# ESP_LoRa_ScaleSansotta.net
KiCad netlist of a schematic drawn in EAGLE
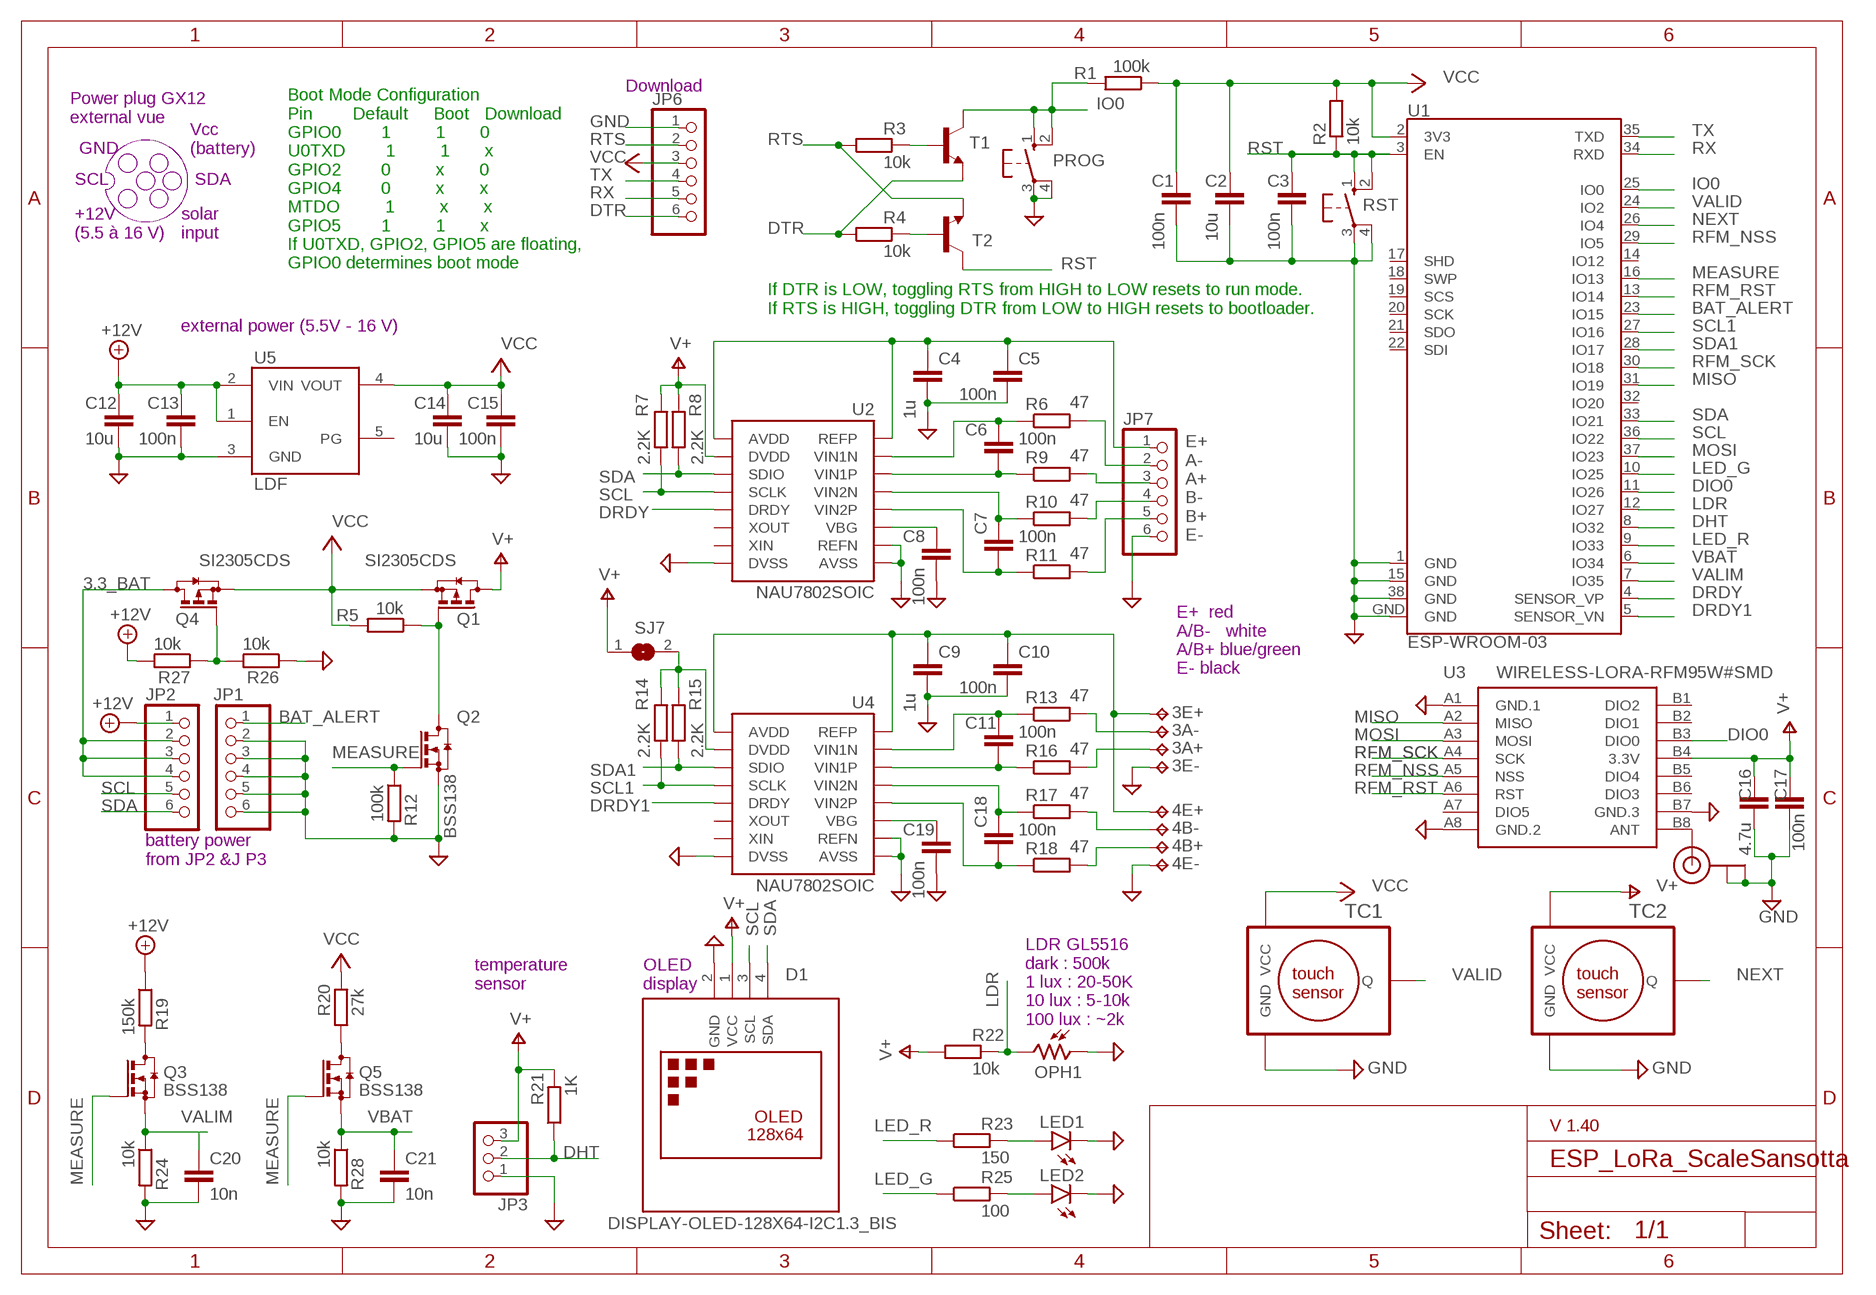
[diagram p0: schematic, sheet 1]

(export (version "E")
  (design (tool "Eeschema 10.0.6"))
  (components
    (comp (ref "3A+")
      (value "TPTP17SQ")
      (footprint "eagle-import:TP17SQ")
      (libsource (lib "eagle-import") (part "TPTP17SQ"))
    )
    (comp (ref "3A-")
      (value "TPTP17SQ")
      (footprint "eagle-import:TP17SQ")
      (libsource (lib "eagle-import") (part "TPTP17SQ"))
    )
    (comp (ref "3E+")
      (value "TPTP17SQ")
      (footprint "eagle-import:TP17SQ")
      (libsource (lib "eagle-import") (part "TPTP17SQ"))
    )
    (comp (ref "3E-")
      (value "TPTP17SQ")
      (footprint "eagle-import:TP17SQ")
      (libsource (lib "eagle-import") (part "TPTP17SQ"))
    )
    (comp (ref "4B+")
      (value "TPTP17SQ")
      (footprint "eagle-import:TP17SQ")
      (libsource (lib "eagle-import") (part "TPTP17SQ"))
    )
    (comp (ref "4B-")
      (value "TPTP17SQ")
      (footprint "eagle-import:TP17SQ")
      (libsource (lib "eagle-import") (part "TPTP17SQ"))
    )
    (comp (ref "4E+")
      (value "TPTP17SQ")
      (footprint "eagle-import:TP17SQ")
      (libsource (lib "eagle-import") (part "TPTP17SQ"))
    )
    (comp (ref "4E-")
      (value "TPTP17SQ")
      (footprint "eagle-import:TP17SQ")
      (libsource (lib "eagle-import") (part "TPTP17SQ"))
    )
    (comp (ref "C1")
      (value "100n")
      (footprint "eagle-import:C1206")
      (libsource (lib "eagle-import") (part "CC1206"))
    )
    (comp (ref "C2")
      (value "10u")
      (footprint "eagle-import:C1210")
      (libsource (lib "eagle-import") (part "CC1210"))
    )
    (comp (ref "C3")
      (value "100n")
      (footprint "eagle-import:C1206")
      (libsource (lib "eagle-import") (part "CC1206"))
    )
    (comp (ref "C4")
      (value "1u")
      (footprint "eagle-import:C1210")
      (libsource (lib "eagle-import") (part "CC1210"))
    )
    (comp (ref "C5")
      (value "100n")
      (footprint "eagle-import:C1206")
      (libsource (lib "eagle-import") (part "CC1206"))
    )
    (comp (ref "C6")
      (value "100n")
      (footprint "eagle-import:C1206")
      (libsource (lib "eagle-import") (part "CC1206"))
    )
    (comp (ref "C7")
      (value "100n")
      (footprint "eagle-import:C1206")
      (libsource (lib "eagle-import") (part "CC1206"))
    )
    (comp (ref "C8")
      (value "100n")
      (footprint "eagle-import:C1206")
      (libsource (lib "eagle-import") (part "CC1206"))
    )
    (comp (ref "C9")
      (value "1u")
      (footprint "eagle-import:C1210")
      (libsource (lib "eagle-import") (part "CC1210"))
    )
    (comp (ref "C10")
      (value "100n")
      (footprint "eagle-import:C1206")
      (libsource (lib "eagle-import") (part "CC1206"))
    )
    (comp (ref "C11")
      (value "100n")
      (footprint "eagle-import:C1206")
      (libsource (lib "eagle-import") (part "CC1206"))
    )
    (comp (ref "C12")
      (value "10u")
      (footprint "eagle-import:C1210")
      (libsource (lib "eagle-import") (part "CC1210"))
    )
    (comp (ref "C13")
      (value "100n")
      (footprint "eagle-import:C1206")
      (libsource (lib "eagle-import") (part "CC1206"))
    )
    (comp (ref "C14")
      (value "10u")
      (footprint "eagle-import:C1210")
      (libsource (lib "eagle-import") (part "CC1210"))
    )
    (comp (ref "C15")
      (value "100n")
      (footprint "eagle-import:C1206")
      (libsource (lib "eagle-import") (part "CC1206"))
    )
    (comp (ref "C16")
      (value "4.7u")
      (footprint "eagle-import:C1210")
      (libsource (lib "eagle-import") (part "CC1210"))
    )
    (comp (ref "C17")
      (value "100n")
      (footprint "eagle-import:C1206")
      (libsource (lib "eagle-import") (part "CC1206"))
    )
    (comp (ref "C18")
      (value "100n")
      (footprint "eagle-import:C1206")
      (libsource (lib "eagle-import") (part "CC1206"))
    )
    (comp (ref "C19")
      (value "100n")
      (footprint "eagle-import:C1206")
      (libsource (lib "eagle-import") (part "CC1206"))
    )
    (comp (ref "C20")
      (value "10n")
      (footprint "eagle-import:C1206")
      (libsource (lib "eagle-import") (part "CC1206"))
    )
    (comp (ref "C21")
      (value "10n")
      (footprint "eagle-import:C1206")
      (libsource (lib "eagle-import") (part "CC1206"))
    )
    (comp (ref "D1")
      (value "DISPLAY-OLED-128X64-I2C1.3_BIS")
      (footprint "eagle-import:DISPLAY-OLED-128X64-1.3-I2C_BIS")
      (libsource (lib "eagle-import") (part "DISPLAY-OLED-128X64-I2C1.3_BIS"))
    )
    (comp (ref "J1")
      (value "U.FL")
      (footprint "eagle-import:U.FL")
      (libsource (lib "eagle-import") (part "U.FL"))
    )
    (comp (ref "JP1")
      (value "PINHD-1X6")
      (footprint "eagle-import:1X06")
      (libsource (lib "eagle-import") (part "PINHD-1X6"))
    )
    (comp (ref "JP2")
      (value "PINHD-1X6")
      (footprint "eagle-import:1X06")
      (libsource (lib "eagle-import") (part "PINHD-1X6"))
    )
    (comp (ref "JP3")
      (value "PINHD-1X3")
      (footprint "eagle-import:1X03")
      (libsource (lib "eagle-import") (part "PINHD-1X3"))
    )
    (comp (ref "JP6")
      (value "PINHD-1X6")
      (footprint "eagle-import:1X06")
      (libsource (lib "eagle-import") (part "PINHD-1X6"))
    )
    (comp (ref "JP7")
      (value "PINHD-1X6")
      (footprint "eagle-import:1X06")
      (libsource (lib "eagle-import") (part "PINHD-1X6"))
    )
    (comp (ref "LED1")
      (value "LEDSMT1206")
      (footprint "eagle-import:1206")
      (libsource (lib "eagle-import") (part "LEDSMT1206"))
    )
    (comp (ref "LED2")
      (value "LEDSMT1206")
      (footprint "eagle-import:1206")
      (libsource (lib "eagle-import") (part "LEDSMT1206"))
    )
    (comp (ref "OPH1")
      (value "VT93N2")
      (footprint "eagle-import:VT900")
      (libsource (lib "eagle-import") (part "VT93N2"))
    )
    (comp (ref "PROG")
      (value "10-XX")
      (footprint "eagle-import:B3F-10XX")
      (fields (field (name "MPN") "B3F-1000"))
      (libsource (lib "eagle-import") (part "10-XX"))
    )
    (comp (ref "Q1")
      (value "SI2305CDS")
      (footprint "eagle-import:SOT23")
      (libsource (lib "eagle-import") (part "SI2305CDS"))
    )
    (comp (ref "Q2")
      (value "BSS138")
      (footprint "eagle-import:SOT23")
      (libsource (lib "eagle-import") (part "BSS138"))
    )
    (comp (ref "Q3")
      (value "BSS138")
      (footprint "eagle-import:SOT23")
      (libsource (lib "eagle-import") (part "BSS138"))
    )
    (comp (ref "Q4")
      (value "SI2305CDS")
      (footprint "eagle-import:SOT23")
      (libsource (lib "eagle-import") (part "SI2305CDS"))
    )
    (comp (ref "Q5")
      (value "BSS138")
      (footprint "eagle-import:SOT23")
      (libsource (lib "eagle-import") (part "BSS138"))
    )
    (comp (ref "R1")
      (value "100k")
      (footprint "eagle-import:R1206")
      (libsource (lib "eagle-import") (part "RR1206"))
    )
    (comp (ref "R2")
      (value "10k")
      (footprint "eagle-import:R1206")
      (libsource (lib "eagle-import") (part "RR1206"))
    )
    (comp (ref "R3")
      (value "10k")
      (footprint "eagle-import:R1206")
      (libsource (lib "eagle-import") (part "RR1206"))
    )
    (comp (ref "R4")
      (value "10k")
      (footprint "eagle-import:R1206")
      (libsource (lib "eagle-import") (part "RR1206"))
    )
    (comp (ref "R5")
      (value "10k")
      (footprint "eagle-import:R1206")
      (libsource (lib "eagle-import") (part "RR1206"))
    )
    (comp (ref "R6")
      (value "47")
      (footprint "eagle-import:R1206")
      (libsource (lib "eagle-import") (part "RR1206"))
    )
    (comp (ref "R7")
      (value "2.2K")
      (footprint "eagle-import:R1206")
      (libsource (lib "eagle-import") (part "RR1206"))
    )
    (comp (ref "R8")
      (value "2.2K")
      (footprint "eagle-import:R1206")
      (libsource (lib "eagle-import") (part "RR1206"))
    )
    (comp (ref "R9")
      (value "47")
      (footprint "eagle-import:R1206")
      (libsource (lib "eagle-import") (part "RR1206"))
    )
    (comp (ref "R10")
      (value "47")
      (footprint "eagle-import:R1206")
      (libsource (lib "eagle-import") (part "RR1206"))
    )
    (comp (ref "R11")
      (value "47")
      (footprint "eagle-import:R1206")
      (libsource (lib "eagle-import") (part "RR1206"))
    )
    (comp (ref "R12")
      (value "100k")
      (footprint "eagle-import:R1206")
      (libsource (lib "eagle-import") (part "RR1206"))
    )
    (comp (ref "R13")
      (value "47")
      (footprint "eagle-import:R1206")
      (libsource (lib "eagle-import") (part "RR1206"))
    )
    (comp (ref "R14")
      (value "2.2K")
      (footprint "eagle-import:R1206")
      (libsource (lib "eagle-import") (part "RR1206"))
    )
    (comp (ref "R15")
      (value "2.2K")
      (footprint "eagle-import:R1206")
      (libsource (lib "eagle-import") (part "RR1206"))
    )
    (comp (ref "R16")
      (value "47")
      (footprint "eagle-import:R1206")
      (libsource (lib "eagle-import") (part "RR1206"))
    )
    (comp (ref "R17")
      (value "47")
      (footprint "eagle-import:R1206")
      (libsource (lib "eagle-import") (part "RR1206"))
    )
    (comp (ref "R18")
      (value "47")
      (footprint "eagle-import:R1206")
      (libsource (lib "eagle-import") (part "RR1206"))
    )
    (comp (ref "R19")
      (value "150k")
      (footprint "eagle-import:R1206")
      (libsource (lib "eagle-import") (part "RR1206"))
    )
    (comp (ref "R20")
      (value "27k")
      (footprint "eagle-import:R1206")
      (libsource (lib "eagle-import") (part "RR1206"))
    )
    (comp (ref "R21")
      (value "1K")
      (footprint "eagle-import:R1206")
      (libsource (lib "eagle-import") (part "RR1206"))
    )
    (comp (ref "R22")
      (value "10k")
      (footprint "eagle-import:R1206")
      (libsource (lib "eagle-import") (part "RR1206"))
    )
    (comp (ref "R23")
      (value "150")
      (footprint "eagle-import:R1206")
      (libsource (lib "eagle-import") (part "RR1206"))
    )
    (comp (ref "R24")
      (value "10k")
      (footprint "eagle-import:R1206")
      (libsource (lib "eagle-import") (part "RR1206"))
    )
    (comp (ref "R25")
      (value "100")
      (footprint "eagle-import:R1206")
      (libsource (lib "eagle-import") (part "RR1206"))
    )
    (comp (ref "R26")
      (value "10k")
      (footprint "eagle-import:R1206")
      (libsource (lib "eagle-import") (part "RR1206"))
    )
    (comp (ref "R27")
      (value "10k")
      (footprint "eagle-import:R1206")
      (libsource (lib "eagle-import") (part "RR1206"))
    )
    (comp (ref "R28")
      (value "10k")
      (footprint "eagle-import:R1206")
      (libsource (lib "eagle-import") (part "RR1206"))
    )
    (comp (ref "RST")
      (value "10-XX")
      (footprint "eagle-import:B3F-10XX")
      (fields (field (name "MPN") "B3F-1000"))
      (libsource (lib "eagle-import") (part "10-XX"))
    )
    (comp (ref "SJ7") (value "SJ") (footprint "eagle-import:SJ") (libsource (lib "eagle-import") (part "SJ")))
    (comp (ref "T1")
      (value "MMBT2222ALT1-NPN-SOT23-BEC")
      (footprint "eagle-import:SOT23-BEC")
      (libsource (lib "eagle-import") (part "-NPN-SOT23-BECMMBT2222ALT1"))
    )
    (comp (ref "T2")
      (value "MMBT2222ALT1-NPN-SOT23-BEC")
      (footprint "eagle-import:SOT23-BEC")
      (libsource (lib "eagle-import") (part "-NPN-SOT23-BECMMBT2222ALT1"))
    )
    (comp (ref "TC1")
      (value "TTP223R_H")
      (footprint "eagle-import:TTP233RED_H")
      (libsource (lib "eagle-import") (part "TTP223R_H"))
    )
    (comp (ref "TC2")
      (value "TTP223R_H")
      (footprint "eagle-import:TTP233RED_H")
      (libsource (lib "eagle-import") (part "TTP223R_H"))
    )
    (comp (ref "U1")
      (value "ESP-WROOM-03")
      (footprint "eagle-import:ESP-WROOM-03")
      (libsource (lib "eagle-import") (part "ESP-WROOM-03"))
    )
    (comp (ref "U2")
      (value "NAU7802SOIC")
      (footprint "eagle-import:SO16")
      (libsource (lib "eagle-import") (part "NAU7802SOIC"))
    )
    (comp (ref "U3")
      (value "WIRELESS-LORA-RFM95W#SMD")
      (footprint "eagle-import:WIRELESS-LORA-RFM95W#SMD")
      (libsource (lib "eagle-import") (part "WIRELESS-LORA-RFM95W#SMD"))
    )
    (comp (ref "U4")
      (value "NAU7802SOIC")
      (footprint "eagle-import:SO16")
      (libsource (lib "eagle-import") (part "NAU7802SOIC"))
    )
    (comp (ref "U5")
      (value "LDF3.3")
      (footprint "eagle-import:PPAK")
      (libsource (lib "eagle-import") (part "LDF3.3"))
    )
  )
  (nets
    (net (code "1") (name "+12V") (class "Default")
      (node (ref "C12") (pin "1") (pinfunction "1_1") (pintype "passive"))
      (node (ref "C13") (pin "1") (pinfunction "1_1") (pintype "passive"))
      (node (ref "JP2") (pin "1") (pinfunction "1_1") (pintype "passive"))
      (node (ref "R19") (pin "1") (pinfunction "1_1") (pintype "passive"))
      (node (ref "R27") (pin "2") (pinfunction "2_2") (pintype "passive"))
      (node (ref "U5") (pin "1") (pinfunction "EN_1") (pintype "input"))
      (node (ref "U5") (pin "2") (pinfunction "VIN_2") (pintype "power_in"))
    )
    (net (code "2") (name "/3.3_BAT") (class "Default")
      (node (ref "JP2") (pin "2") (pinfunction "2_2") (pintype "passive"))
      (node (ref "JP2") (pin "3") (pinfunction "3_3") (pintype "passive"))
      (node (ref "JP2") (pin "4") (pinfunction "4_4") (pintype "passive"))
      (node (ref "Q4") (pin "3") (pinfunction "D_3") (pintype "passive"))
    )
    (net (code "3") (name "/BAT_ALERT") (class "Default")
      (node (ref "JP1") (pin "1") (pinfunction "1_1") (pintype "passive"))
      (node (ref "U1") (pin "23") (pinfunction "IO15_23") (pintype "bidirectional"))
    )
    (net (code "4") (name "/DHT") (class "Default")
      (node (ref "JP3") (pin "2") (pinfunction "2_2") (pintype "passive"))
      (node (ref "R21") (pin "1") (pinfunction "1_1") (pintype "passive"))
      (node (ref "U1") (pin "8") (pinfunction "IO32_8") (pintype "bidirectional"))
    )
    (net (code "5") (name "/DIO0") (class "Default")
      (node (ref "U1") (pin "11") (pinfunction "IO26_11") (pintype "bidirectional"))
      (node (ref "U3") (pin "B3") (pinfunction "DIO0_B3") (pintype "bidirectional"))
    )
    (net (code "6") (name "/DRDY") (class "Default")
      (node (ref "U1") (pin "4") (pinfunction "SENSOR_VP_4") (pintype "bidirectional"))
      (node (ref "U2") (pin "12") (pinfunction "DRDY_12") (pintype "bidirectional"))
    )
    (net (code "7") (name "/DRDY1") (class "Default")
      (node (ref "U1") (pin "5") (pinfunction "SENSOR_VN_5") (pintype "bidirectional"))
      (node (ref "U4") (pin "12") (pinfunction "DRDY_12") (pintype "bidirectional"))
    )
    (net (code "8") (name "/DTR") (class "Default")
      (node (ref "JP6") (pin "6") (pinfunction "6_6") (pintype "passive"))
      (node (ref "R4") (pin "1") (pinfunction "1_1") (pintype "passive"))
      (node (ref "T1") (pin "E") (pinfunction "E_E") (pintype "passive"))
    )
    (net (code "9") (name "/IO0") (class "Default")
      (node (ref "PROG") (pin "1") (pinfunction "S_1") (pintype "passive"))
      (node (ref "PROG") (pin "2") (pinfunction "S1_2") (pintype "passive"))
      (node (ref "R1") (pin "2") (pinfunction "2_2") (pintype "passive"))
      (node (ref "T1") (pin "C") (pinfunction "C_C") (pintype "passive"))
      (node (ref "U1") (pin "25") (pinfunction "IO0_25") (pintype "bidirectional"))
    )
    (net (code "10") (name "/LDR") (class "Default")
      (node (ref "OPH1") (pin "2") (pinfunction "2_2") (pintype "passive"))
      (node (ref "R22") (pin "2") (pinfunction "2_2") (pintype "passive"))
      (node (ref "U1") (pin "12") (pinfunction "IO27_12") (pintype "bidirectional"))
    )
    (net (code "11") (name "/LED_G") (class "Default")
      (node (ref "R25") (pin "1") (pinfunction "1_1") (pintype "passive"))
      (node (ref "U1") (pin "10") (pinfunction "IO25_10") (pintype "bidirectional"))
    )
    (net (code "12") (name "/LED_R") (class "Default")
      (node (ref "R23") (pin "1") (pinfunction "1_1") (pintype "passive"))
      (node (ref "U1") (pin "9") (pinfunction "IO33_9") (pintype "bidirectional"))
    )
    (net (code "13") (name "/MEASURE") (class "Default")
      (node (ref "Q2") (pin "1") (pinfunction "G_1") (pintype "passive"))
      (node (ref "Q3") (pin "1") (pinfunction "G_1") (pintype "passive"))
      (node (ref "Q5") (pin "1") (pinfunction "G_1") (pintype "passive"))
      (node (ref "R12") (pin "1") (pinfunction "1_1") (pintype "passive"))
      (node (ref "U1") (pin "16") (pinfunction "IO13_16") (pintype "bidirectional"))
    )
    (net (code "14") (name "/MISO") (class "Default")
      (node (ref "U1") (pin "31") (pinfunction "IO19_31") (pintype "bidirectional"))
      (node (ref "U3") (pin "A2") (pinfunction "MISO_A2") (pintype "bidirectional"))
    )
    (net (code "15") (name "/MOSI") (class "Default")
      (node (ref "U1") (pin "37") (pinfunction "IO23_37") (pintype "bidirectional"))
      (node (ref "U3") (pin "A3") (pinfunction "MOSI_A3") (pintype "bidirectional"))
    )
    (net (code "16") (name "/NEXT") (class "Default")
      (node (ref "TC2") (pin "P$2") (pinfunction "Q_P$2") (pintype "power_in"))
      (node (ref "U1") (pin "26") (pinfunction "IO4_26") (pintype "bidirectional"))
    )
    (net (code "17") (name "/PG") (class "Default")
      (node (ref "U5") (pin "5") (pinfunction "PG_5") (pintype "power_in"))
    )
    (net (code "18") (name "/RFM_NSS") (class "Default")
      (node (ref "U1") (pin "29") (pinfunction "IO5_29") (pintype "bidirectional"))
      (node (ref "U3") (pin "A5") (pinfunction "NSS_A5") (pintype "bidirectional"))
    )
    (net (code "19") (name "/RFM_RST") (class "Default")
      (node (ref "U1") (pin "13") (pinfunction "IO14_13") (pintype "bidirectional"))
      (node (ref "U3") (pin "A6") (pinfunction "RST_A6") (pintype "bidirectional"))
    )
    (net (code "20") (name "/RFM_SCK") (class "Default")
      (node (ref "U1") (pin "30") (pinfunction "IO18_30") (pintype "bidirectional"))
      (node (ref "U3") (pin "A4") (pinfunction "SCK_A4") (pintype "bidirectional"))
    )
    (net (code "21") (name "/RST") (class "Default")
      (node (ref "C3") (pin "1") (pinfunction "1_1") (pintype "passive"))
      (node (ref "R2") (pin "1") (pinfunction "1_1") (pintype "passive"))
      (node (ref "RST") (pin "1") (pinfunction "S_1") (pintype "passive"))
      (node (ref "RST") (pin "2") (pinfunction "S1_2") (pintype "passive"))
      (node (ref "T2") (pin "C") (pinfunction "C_C") (pintype "passive"))
      (node (ref "U1") (pin "3") (pinfunction "EN_3") (pintype "bidirectional"))
    )
    (net (code "22") (name "/RTS") (class "Default")
      (node (ref "JP6") (pin "2") (pinfunction "2_2") (pintype "passive"))
      (node (ref "R3") (pin "1") (pinfunction "1_1") (pintype "passive"))
      (node (ref "T2") (pin "E") (pinfunction "E_E") (pintype "passive"))
    )
    (net (code "23") (name "/RX") (class "Default")
      (node (ref "JP6") (pin "5") (pinfunction "5_5") (pintype "passive"))
      (node (ref "U1") (pin "34") (pinfunction "RXD_34") (pintype "bidirectional"))
    )
    (net (code "24") (name "/SCL") (class "Default")
      (node (ref "D1") (pin "3") (pinfunction "SCL_3") (pintype "bidirectional"))
      (node (ref "JP2") (pin "5") (pinfunction "5_5") (pintype "passive"))
      (node (ref "R7") (pin "1") (pinfunction "1_1") (pintype "passive"))
      (node (ref "U1") (pin "36") (pinfunction "IO22_36") (pintype "bidirectional"))
      (node (ref "U2") (pin "13") (pinfunction "SCLK_13") (pintype "bidirectional"))
    )
    (net (code "25") (name "/SCL1") (class "Default")
      (node (ref "R14") (pin "1") (pinfunction "1_1") (pintype "passive"))
      (node (ref "U1") (pin "27") (pinfunction "IO16_27") (pintype "bidirectional"))
      (node (ref "U4") (pin "13") (pinfunction "SCLK_13") (pintype "bidirectional"))
    )
    (net (code "26") (name "/SDA") (class "Default")
      (node (ref "D1") (pin "4") (pinfunction "SDA_4") (pintype "bidirectional"))
      (node (ref "JP2") (pin "6") (pinfunction "6_6") (pintype "passive"))
      (node (ref "R8") (pin "1") (pinfunction "1_1") (pintype "passive"))
      (node (ref "U1") (pin "33") (pinfunction "IO21_33") (pintype "bidirectional"))
      (node (ref "U2") (pin "14") (pinfunction "SDIO_14") (pintype "bidirectional"))
    )
    (net (code "27") (name "/SDA1") (class "Default")
      (node (ref "R15") (pin "1") (pinfunction "1_1") (pintype "passive"))
      (node (ref "U1") (pin "28") (pinfunction "IO17_28") (pintype "bidirectional"))
      (node (ref "U4") (pin "14") (pinfunction "SDIO_14") (pintype "bidirectional"))
    )
    (net (code "28") (name "/TX") (class "Default")
      (node (ref "JP6") (pin "4") (pinfunction "4_4") (pintype "passive"))
      (node (ref "U1") (pin "35") (pinfunction "TXD_35") (pintype "bidirectional"))
    )
    (net (code "29") (name "/VALID") (class "Default")
      (node (ref "TC1") (pin "P$2") (pinfunction "Q_P$2") (pintype "power_in"))
      (node (ref "U1") (pin "24") (pinfunction "IO2_24") (pintype "bidirectional"))
    )
    (net (code "30") (name "/VALIM") (class "Default")
      (node (ref "C20") (pin "1") (pinfunction "1_1") (pintype "passive"))
      (node (ref "Q3") (pin "2") (pinfunction "S_2") (pintype "passive"))
      (node (ref "R24") (pin "1") (pinfunction "1_1") (pintype "passive"))
      (node (ref "U1") (pin "7") (pinfunction "IO35_7") (pintype "bidirectional"))
    )
    (net (code "31") (name "/VBAT") (class "Default")
      (node (ref "C21") (pin "1") (pinfunction "1_1") (pintype "passive"))
      (node (ref "Q5") (pin "2") (pinfunction "S_2") (pintype "passive"))
      (node (ref "R28") (pin "1") (pinfunction "1_1") (pintype "passive"))
      (node (ref "U1") (pin "6") (pinfunction "IO34_6") (pintype "bidirectional"))
    )
    (net (code "32") (name "GND") (class "Default")
      (node (ref "3E-") (pin "TP") (pinfunction "TP_TP") (pintype "input"))
      (node (ref "4E-") (pin "TP") (pinfunction "TP_TP") (pintype "input"))
      (node (ref "C1") (pin "2") (pinfunction "2_2") (pintype "passive"))
      (node (ref "C10") (pin "2") (pinfunction "2_2") (pintype "passive"))
      (node (ref "C12") (pin "2") (pinfunction "2_2") (pintype "passive"))
      (node (ref "C13") (pin "2") (pinfunction "2_2") (pintype "passive"))
      (node (ref "C14") (pin "2") (pinfunction "2_2") (pintype "passive"))
      (node (ref "C15") (pin "2") (pinfunction "2_2") (pintype "passive"))
      (node (ref "C16") (pin "2") (pinfunction "2_2") (pintype "passive"))
      (node (ref "C17") (pin "2") (pinfunction "2_2") (pintype "passive"))
      (node (ref "C19") (pin "2") (pinfunction "2_2") (pintype "passive"))
      (node (ref "C2") (pin "2") (pinfunction "2_2") (pintype "passive"))
      (node (ref "C20") (pin "2") (pinfunction "2_2") (pintype "passive"))
      (node (ref "C21") (pin "2") (pinfunction "2_2") (pintype "passive"))
      (node (ref "C3") (pin "2") (pinfunction "2_2") (pintype "passive"))
      (node (ref "C4") (pin "2") (pinfunction "2_2") (pintype "passive"))
      (node (ref "C5") (pin "2") (pinfunction "2_2") (pintype "passive"))
      (node (ref "C8") (pin "2") (pinfunction "2_2") (pintype "passive"))
      (node (ref "C9") (pin "2") (pinfunction "2_2") (pintype "passive"))
      (node (ref "D1") (pin "2") (pinfunction "GND_2") (pintype "power_in"))
      (node (ref "J1") (pin "1") (pinfunction "GND_1") (pintype "passive"))
      (node (ref "J1") (pin "2") (pinfunction "GND_2") (pintype "passive"))
      (node (ref "JP1") (pin "2") (pinfunction "2_2") (pintype "passive"))
      (node (ref "JP1") (pin "3") (pinfunction "3_3") (pintype "passive"))
      (node (ref "JP1") (pin "4") (pinfunction "4_4") (pintype "passive"))
      (node (ref "JP1") (pin "5") (pinfunction "5_5") (pintype "passive"))
      (node (ref "JP1") (pin "6") (pinfunction "6_6") (pintype "passive"))
      (node (ref "JP3") (pin "1") (pinfunction "1_1") (pintype "passive"))
      (node (ref "JP6") (pin "1") (pinfunction "1_1") (pintype "passive"))
      (node (ref "JP7") (pin "6") (pinfunction "6_6") (pintype "passive"))
      (node (ref "LED1") (pin "C") (pinfunction "C_C") (pintype "passive"))
      (node (ref "LED2") (pin "C") (pinfunction "C_C") (pintype "passive"))
      (node (ref "OPH1") (pin "1") (pinfunction "1_1") (pintype "passive"))
      (node (ref "PROG") (pin "3") (pinfunction "P_3") (pintype "passive"))
      (node (ref "PROG") (pin "4") (pinfunction "P1_4") (pintype "passive"))
      (node (ref "Q2") (pin "2") (pinfunction "S_2") (pintype "passive"))
      (node (ref "R12") (pin "2") (pinfunction "2_2") (pintype "passive"))
      (node (ref "R24") (pin "2") (pinfunction "2_2") (pintype "passive"))
      (node (ref "R26") (pin "1") (pinfunction "1_1") (pintype "passive"))
      (node (ref "R28") (pin "2") (pinfunction "2_2") (pintype "passive"))
      (node (ref "RST") (pin "3") (pinfunction "P_3") (pintype "passive"))
      (node (ref "RST") (pin "4") (pinfunction "P1_4") (pintype "passive"))
      (node (ref "TC1") (pin "P$3") (pinfunction "GND_P$3") (pintype "power_in"))
      (node (ref "TC2") (pin "P$3") (pinfunction "GND_P$3") (pintype "power_in"))
      (node (ref "U1") (pin "1") (pinfunction "GND_1") (pintype "bidirectional"))
      (node (ref "U1") (pin "15") (pinfunction "GND_15") (pintype "bidirectional"))
      (node (ref "U1") (pin "38") (pinfunction "GND_38") (pintype "bidirectional"))
      (node (ref "U1") (pin "GND") (pinfunction "GND_GND") (pintype "bidirectional"))
      (node (ref "U2") (pin "7") (pinfunction "REFN_7") (pintype "bidirectional"))
      (node (ref "U2") (pin "8") (pinfunction "AVSS_8") (pintype "bidirectional"))
      (node (ref "U2") (pin "9") (pinfunction "DVSS_9") (pintype "bidirectional"))
      (node (ref "U3") (pin "A1") (pinfunction "GND.1_A1") (pintype "power_in"))
      (node (ref "U3") (pin "A8") (pinfunction "GND.2_A8") (pintype "power_in"))
      (node (ref "U3") (pin "B7") (pinfunction "GND.3_B7") (pintype "power_in"))
      (node (ref "U4") (pin "7") (pinfunction "REFN_7") (pintype "bidirectional"))
      (node (ref "U4") (pin "8") (pinfunction "AVSS_8") (pintype "bidirectional"))
      (node (ref "U4") (pin "9") (pinfunction "DVSS_9") (pintype "bidirectional"))
      (node (ref "U5") (pin "3") (pinfunction "GND_3") (pintype "power_in"))
    )
    (net (code "33") (name "Net-(3A+-PadTP)") (class "Default")
      (node (ref "3A+") (pin "TP") (pinfunction "TP_TP") (pintype "input"))
      (node (ref "R16") (pin "2") (pinfunction "2_2") (pintype "passive"))
    )
    (net (code "34") (name "Net-(3A--PadTP)") (class "Default")
      (node (ref "3A-") (pin "TP") (pinfunction "TP_TP") (pintype "input"))
      (node (ref "R13") (pin "2") (pinfunction "2_2") (pintype "passive"))
    )
    (net (code "35") (name "Net-(4B+-PadTP)") (class "Default")
      (node (ref "4B+") (pin "TP") (pinfunction "TP_TP") (pintype "input"))
      (node (ref "R18") (pin "2") (pinfunction "2_2") (pintype "passive"))
    )
    (net (code "36") (name "Net-(4B--PadTP)") (class "Default")
      (node (ref "4B-") (pin "TP") (pinfunction "TP_TP") (pintype "input"))
      (node (ref "R17") (pin "2") (pinfunction "2_2") (pintype "passive"))
    )
    (net (code "37") (name "Net-(J1-SIGNAL)") (class "Default")
      (node (ref "J1") (pin "3") (pinfunction "SIGNAL_3") (pintype "passive"))
      (node (ref "U3") (pin "B8") (pinfunction "ANT_B8") (pintype "passive"))
    )
    (net (code "38") (name "Net-(JP7-Pad2)") (class "Default")
      (node (ref "JP7") (pin "2") (pinfunction "2_2") (pintype "passive"))
      (node (ref "R6") (pin "2") (pinfunction "2_2") (pintype "passive"))
    )
    (net (code "39") (name "Net-(JP7-Pad3)") (class "Default")
      (node (ref "JP7") (pin "3") (pinfunction "3_3") (pintype "passive"))
      (node (ref "R9") (pin "2") (pinfunction "2_2") (pintype "passive"))
    )
    (net (code "40") (name "Net-(JP7-Pad4)") (class "Default")
      (node (ref "JP7") (pin "4") (pinfunction "4_4") (pintype "passive"))
      (node (ref "R10") (pin "2") (pinfunction "2_2") (pintype "passive"))
    )
    (net (code "41") (name "Net-(JP7-Pad5)") (class "Default")
      (node (ref "JP7") (pin "5") (pinfunction "5_5") (pintype "passive"))
      (node (ref "R11") (pin "2") (pinfunction "2_2") (pintype "passive"))
    )
    (net (code "42") (name "Net-(LED1-PadA)") (class "Default")
      (node (ref "LED1") (pin "A") (pinfunction "A_A") (pintype "passive"))
      (node (ref "R23") (pin "2") (pinfunction "2_2") (pintype "passive"))
    )
    (net (code "43") (name "Net-(LED2-PadA)") (class "Default")
      (node (ref "LED2") (pin "A") (pinfunction "A_A") (pintype "passive"))
      (node (ref "R25") (pin "2") (pinfunction "2_2") (pintype "passive"))
    )
    (net (code "44") (name "Net-(Q1-G)") (class "Default")
      (node (ref "Q1") (pin "1") (pinfunction "G_1") (pintype "passive"))
      (node (ref "Q2") (pin "3") (pinfunction "D_3") (pintype "passive"))
      (node (ref "R5") (pin "1") (pinfunction "1_1") (pintype "passive"))
    )
    (net (code "45") (name "Net-(Q3-D)") (class "Default")
      (node (ref "Q3") (pin "3") (pinfunction "D_3") (pintype "passive"))
      (node (ref "R19") (pin "2") (pinfunction "2_2") (pintype "passive"))
    )
    (net (code "46") (name "Net-(Q4-G)") (class "Default")
      (node (ref "Q4") (pin "1") (pinfunction "G_1") (pintype "passive"))
      (node (ref "R26") (pin "2") (pinfunction "2_2") (pintype "passive"))
      (node (ref "R27") (pin "1") (pinfunction "1_1") (pintype "passive"))
    )
    (net (code "47") (name "Net-(Q5-D)") (class "Default")
      (node (ref "Q5") (pin "3") (pinfunction "D_3") (pintype "passive"))
      (node (ref "R20") (pin "1") (pinfunction "1_1") (pintype "passive"))
    )
    (net (code "48") (name "Net-(R3-Pad2)") (class "Default")
      (node (ref "R3") (pin "2") (pinfunction "2_2") (pintype "passive"))
      (node (ref "T1") (pin "B") (pinfunction "B_B") (pintype "passive"))
    )
    (net (code "49") (name "Net-(R4-Pad2)") (class "Default")
      (node (ref "R4") (pin "2") (pinfunction "2_2") (pintype "passive"))
      (node (ref "T2") (pin "B") (pinfunction "B_B") (pintype "passive"))
    )
    (net (code "50") (name "Net-(U2-AVDD)") (class "Default")
      (node (ref "C4") (pin "1") (pinfunction "1_1") (pintype "passive"))
      (node (ref "C5") (pin "1") (pinfunction "1_1") (pintype "passive"))
      (node (ref "JP7") (pin "1") (pinfunction "1_1") (pintype "passive"))
      (node (ref "U2") (pin "1") (pinfunction "REFP_1") (pintype "bidirectional"))
      (node (ref "U2") (pin "16") (pinfunction "AVDD_16") (pintype "bidirectional"))
    )
    (net (code "51") (name "Net-(U2-VBG)") (class "Default")
      (node (ref "C8") (pin "1") (pinfunction "1_1") (pintype "passive"))
      (node (ref "U2") (pin "6") (pinfunction "VBG_6") (pintype "bidirectional"))
    )
    (net (code "52") (name "Net-(U2-VIN1N)") (class "Default")
      (node (ref "C6") (pin "1") (pinfunction "1_1") (pintype "passive"))
      (node (ref "R6") (pin "1") (pinfunction "1_1") (pintype "passive"))
      (node (ref "U2") (pin "2") (pinfunction "VIN1N_2") (pintype "bidirectional"))
    )
    (net (code "53") (name "Net-(U2-VIN1P)") (class "Default")
      (node (ref "C6") (pin "2") (pinfunction "2_2") (pintype "passive"))
      (node (ref "R9") (pin "1") (pinfunction "1_1") (pintype "passive"))
      (node (ref "U2") (pin "3") (pinfunction "VIN1P_3") (pintype "bidirectional"))
    )
    (net (code "54") (name "Net-(U2-VIN2N)") (class "Default")
      (node (ref "C7") (pin "1") (pinfunction "1_1") (pintype "passive"))
      (node (ref "R10") (pin "1") (pinfunction "1_1") (pintype "passive"))
      (node (ref "U2") (pin "4") (pinfunction "VIN2N_4") (pintype "bidirectional"))
    )
    (net (code "55") (name "Net-(U2-VIN2P)") (class "Default")
      (node (ref "C7") (pin "2") (pinfunction "2_2") (pintype "passive"))
      (node (ref "R11") (pin "1") (pinfunction "1_1") (pintype "passive"))
      (node (ref "U2") (pin "5") (pinfunction "VIN2P_5") (pintype "bidirectional"))
    )
    (net (code "56") (name "Net-(U4-AVDD)") (class "Default")
      (node (ref "3E+") (pin "TP") (pinfunction "TP_TP") (pintype "input"))
      (node (ref "4E+") (pin "TP") (pinfunction "TP_TP") (pintype "input"))
      (node (ref "C10") (pin "1") (pinfunction "1_1") (pintype "passive"))
      (node (ref "C9") (pin "1") (pinfunction "1_1") (pintype "passive"))
      (node (ref "U4") (pin "1") (pinfunction "REFP_1") (pintype "bidirectional"))
      (node (ref "U4") (pin "16") (pinfunction "AVDD_16") (pintype "bidirectional"))
    )
    (net (code "57") (name "Net-(U4-DVDD)") (class "Default")
      (node (ref "R14") (pin "2") (pinfunction "2_2") (pintype "passive"))
      (node (ref "R15") (pin "2") (pinfunction "2_2") (pintype "passive"))
      (node (ref "SJ7") (pin "2") (pinfunction "2_2") (pintype "passive"))
      (node (ref "U4") (pin "15") (pinfunction "DVDD_15") (pintype "bidirectional"))
    )
    (net (code "58") (name "Net-(U4-VBG)") (class "Default")
      (node (ref "C19") (pin "1") (pinfunction "1_1") (pintype "passive"))
      (node (ref "U4") (pin "6") (pinfunction "VBG_6") (pintype "bidirectional"))
    )
    (net (code "59") (name "Net-(U4-VIN1N)") (class "Default")
      (node (ref "C11") (pin "1") (pinfunction "1_1") (pintype "passive"))
      (node (ref "R13") (pin "1") (pinfunction "1_1") (pintype "passive"))
      (node (ref "U4") (pin "2") (pinfunction "VIN1N_2") (pintype "bidirectional"))
    )
    (net (code "60") (name "Net-(U4-VIN1P)") (class "Default")
      (node (ref "C11") (pin "2") (pinfunction "2_2") (pintype "passive"))
      (node (ref "R16") (pin "1") (pinfunction "1_1") (pintype "passive"))
      (node (ref "U4") (pin "3") (pinfunction "VIN1P_3") (pintype "bidirectional"))
    )
    (net (code "61") (name "Net-(U4-VIN2N)") (class "Default")
      (node (ref "C18") (pin "1") (pinfunction "1_1") (pintype "passive"))
      (node (ref "R17") (pin "1") (pinfunction "1_1") (pintype "passive"))
      (node (ref "U4") (pin "4") (pinfunction "VIN2N_4") (pintype "bidirectional"))
    )
    (net (code "62") (name "Net-(U4-VIN2P)") (class "Default")
      (node (ref "C18") (pin "2") (pinfunction "2_2") (pintype "passive"))
      (node (ref "R18") (pin "1") (pinfunction "1_1") (pintype "passive"))
      (node (ref "U4") (pin "5") (pinfunction "VIN2P_5") (pintype "bidirectional"))
    )
    (net (code "63") (name "V+") (class "Default")
      (node (ref "C16") (pin "1") (pinfunction "1_1") (pintype "passive"))
      (node (ref "C17") (pin "1") (pinfunction "1_1") (pintype "passive"))
      (node (ref "D1") (pin "1") (pinfunction "VCC_1") (pintype "power_in"))
      (node (ref "JP3") (pin "3") (pinfunction "3_3") (pintype "passive"))
      (node (ref "Q1") (pin "3") (pinfunction "D_3") (pintype "passive"))
      (node (ref "R21") (pin "2") (pinfunction "2_2") (pintype "passive"))
      (node (ref "R22") (pin "1") (pinfunction "1_1") (pintype "passive"))
      (node (ref "R7") (pin "2") (pinfunction "2_2") (pintype "passive"))
      (node (ref "R8") (pin "2") (pinfunction "2_2") (pintype "passive"))
      (node (ref "SJ7") (pin "1") (pinfunction "1_1") (pintype "passive"))
      (node (ref "TC2") (pin "P$1") (pinfunction "VCC_P$1") (pintype "power_in"))
      (node (ref "U2") (pin "15") (pinfunction "DVDD_15") (pintype "bidirectional"))
      (node (ref "U3") (pin "B4") (pinfunction "3.3V_B4") (pintype "power_in"))
    )
    (net (code "64") (name "VCC") (class "Default")
      (node (ref "C1") (pin "1") (pinfunction "1_1") (pintype "passive"))
      (node (ref "C14") (pin "1") (pinfunction "1_1") (pintype "passive"))
      (node (ref "C15") (pin "1") (pinfunction "1_1") (pintype "passive"))
      (node (ref "C2") (pin "1") (pinfunction "1_1") (pintype "passive"))
      (node (ref "JP6") (pin "3") (pinfunction "3_3") (pintype "passive"))
      (node (ref "Q1") (pin "2") (pinfunction "S_2") (pintype "passive"))
      (node (ref "Q4") (pin "2") (pinfunction "S_2") (pintype "passive"))
      (node (ref "R1") (pin "1") (pinfunction "1_1") (pintype "passive"))
      (node (ref "R2") (pin "2") (pinfunction "2_2") (pintype "passive"))
      (node (ref "R20") (pin "2") (pinfunction "2_2") (pintype "passive"))
      (node (ref "R5") (pin "2") (pinfunction "2_2") (pintype "passive"))
      (node (ref "TC1") (pin "P$1") (pinfunction "VCC_P$1") (pintype "power_in"))
      (node (ref "U1") (pin "2") (pinfunction "3V3_2") (pintype "bidirectional"))
      (node (ref "U5") (pin "4") (pinfunction "VOUT_4") (pintype "power_in"))
    )
    (net (code "65") (name "unconnected-(U1-IO12-Pad14)") (class "Default")
      (node (ref "U1") (pin "14") (pinfunction "IO12_14") (pintype "bidirectional"))
    )
    (net (code "66") (name "unconnected-(U1-IO20-Pad32)") (class "Default")
      (node (ref "U1") (pin "32") (pinfunction "IO20_32") (pintype "bidirectional"))
    )
    (net (code "67") (name "unconnected-(U1-SCK-Pad20)") (class "Default")
      (node (ref "U1") (pin "20") (pinfunction "SCK_20") (pintype "bidirectional"))
    )
    (net (code "68") (name "unconnected-(U1-SCS-Pad19)") (class "Default")
      (node (ref "U1") (pin "19") (pinfunction "SCS_19") (pintype "bidirectional"))
    )
    (net (code "69") (name "unconnected-(U1-SDI-Pad22)") (class "Default")
      (node (ref "U1") (pin "22") (pinfunction "SDI_22") (pintype "bidirectional"))
    )
    (net (code "70") (name "unconnected-(U1-SDO-Pad21)") (class "Default")
      (node (ref "U1") (pin "21") (pinfunction "SDO_21") (pintype "bidirectional"))
    )
    (net (code "71") (name "unconnected-(U1-SHD-Pad17)") (class "Default")
      (node (ref "U1") (pin "17") (pinfunction "SHD_17") (pintype "bidirectional"))
    )
    (net (code "72") (name "unconnected-(U1-SWP-Pad18)") (class "Default")
      (node (ref "U1") (pin "18") (pinfunction "SWP_18") (pintype "bidirectional"))
    )
    (net (code "73") (name "unconnected-(U2-XIN-Pad10)") (class "Default")
      (node (ref "U2") (pin "10") (pinfunction "XIN_10") (pintype "bidirectional"))
    )
    (net (code "74") (name "unconnected-(U2-XOUT-Pad11)") (class "Default")
      (node (ref "U2") (pin "11") (pinfunction "XOUT_11") (pintype "bidirectional"))
    )
    (net (code "75") (name "unconnected-(U3-DIO1-PadB2)") (class "Default")
      (node (ref "U3") (pin "B2") (pinfunction "DIO1_B2") (pintype "bidirectional"))
    )
    (net (code "76") (name "unconnected-(U3-DIO2-PadB1)") (class "Default")
      (node (ref "U3") (pin "B1") (pinfunction "DIO2_B1") (pintype "bidirectional"))
    )
    (net (code "77") (name "unconnected-(U3-DIO3-PadB6)") (class "Default")
      (node (ref "U3") (pin "B6") (pinfunction "DIO3_B6") (pintype "bidirectional"))
    )
    (net (code "78") (name "unconnected-(U3-DIO4-PadB5)") (class "Default")
      (node (ref "U3") (pin "B5") (pinfunction "DIO4_B5") (pintype "bidirectional"))
    )
    (net (code "79") (name "unconnected-(U3-DIO5-PadA7)") (class "Default")
      (node (ref "U3") (pin "A7") (pinfunction "DIO5_A7") (pintype "bidirectional"))
    )
    (net (code "80") (name "unconnected-(U4-XIN-Pad10)") (class "Default")
      (node (ref "U4") (pin "10") (pinfunction "XIN_10") (pintype "bidirectional"))
    )
    (net (code "81") (name "unconnected-(U4-XOUT-Pad11)") (class "Default")
      (node (ref "U4") (pin "11") (pinfunction "XOUT_11") (pintype "bidirectional"))
    )
  )
)
